# Sheet3.net
KiCad netlist of a schematic drawn in Altium Designer
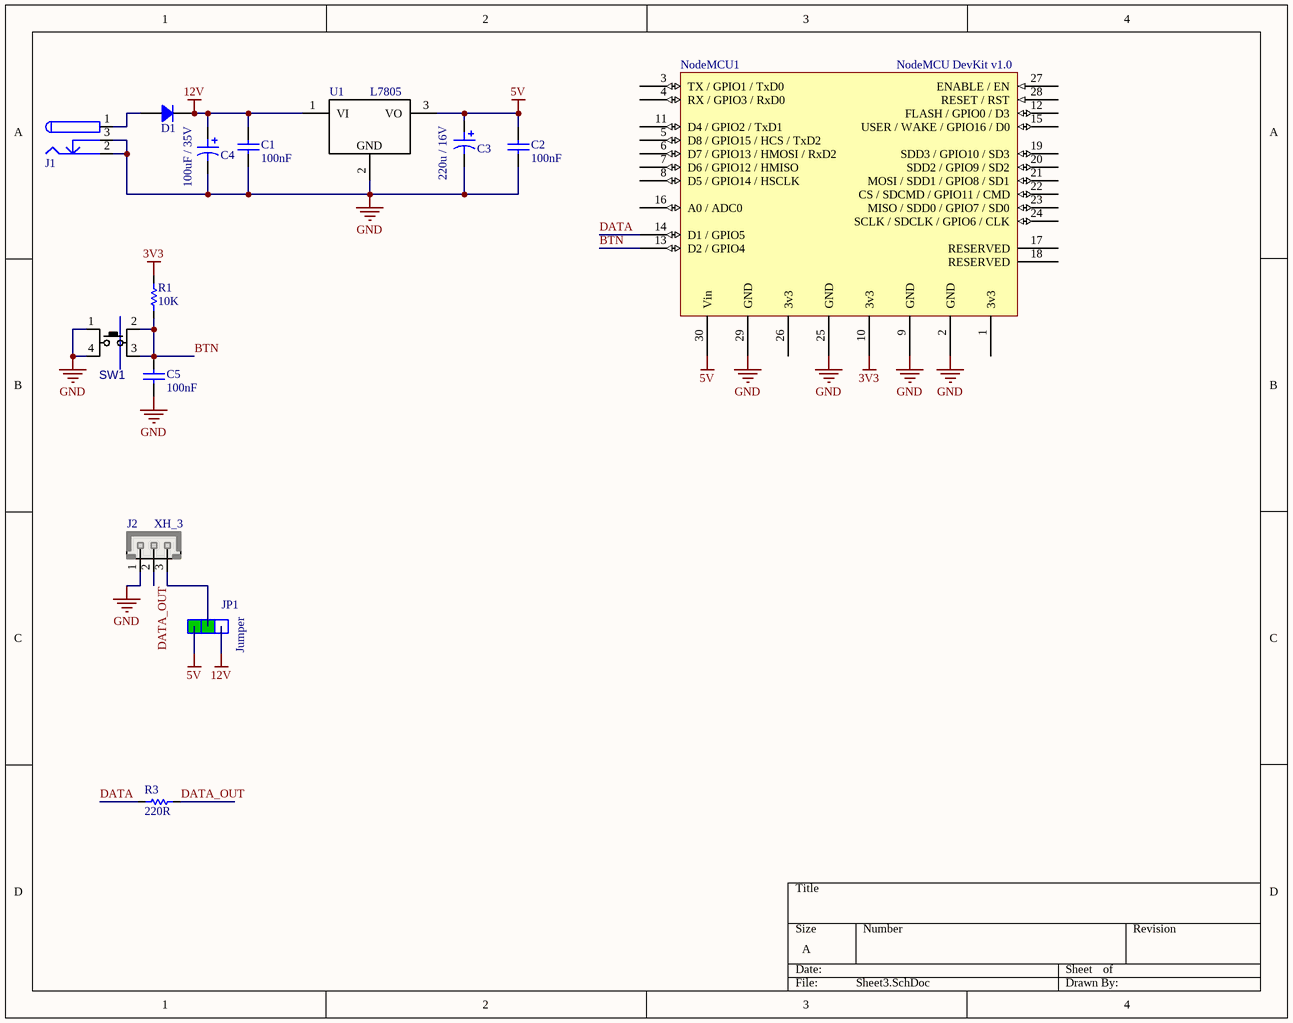
[diagram p0: Sheet3.SchDoc]

(export (version "E")
  (design (tool "Eeschema 10.0.6"))
  (components
    (comp (ref "C1")
      (value "100nF")
      (footprint "CAPC4817X12N")
      (description "CAP 1206")
      (fields (field (name "DESIGNER") "Abbas Basereh"))
      (libsource (lib "4_5924601381297062174") (part "CAP SMD 1206"))
    )
    (comp (ref "C2")
      (value "100nF")
      (footprint "CAPC4817X12N")
      (description "CAP 1206")
      (fields (field (name "DESIGNER") "Abbas Basereh"))
      (libsource (lib "4_5924601381297062174") (part "CAP SMD 1206"))
    )
    (comp (ref "C3")
      (value "220u / 16V")
      (footprint "Cap electrolitic radial 8x12-3.5")
      (description "Cap electrolitic radial")
      (fields (field (name "DESIGNER") "Abbas Basereh"))
      (libsource (lib "4_5924601381297062174") (part "Cap ELECTROLITIC TOTAL SIZE"))
    )
    (comp (ref "C4")
      (value "100uF / 35V")
      (footprint "Cap electrolitic radial 10x20-5")
      (description "Cap electrolitic radial")
      (fields (field (name "DESIGNER") "Abbas Basereh"))
      (libsource (lib "4_5924601381297062174") (part "Cap ELECTROLITIC TOTAL SIZE"))
    )
    (comp (ref "C5")
      (value "100nF")
      (footprint "CAPC4817X12N")
      (description "CAP 1206")
      (fields (field (name "DESIGNER") "Abbas Basereh"))
      (libsource (lib "4_5924601381297062174") (part "CAP SMD 1206"))
    )
    (comp (ref "D1")
      (value "1N4007")
      (footprint "DO41 P7.5MM")
      (description "Diode Standard 1000V 1A Through Hole DO-204AL (DO-41)")
      (libsource (lib "Diode") (part "1N4007 (THD)"))
    )
    (comp (ref "J1")
      (value "DC Power Jack")
      (footprint "DC Power Jack 1")
      (description "DC Power Jack. Center Pin 2.5mm. Diameter: 5.7mm")
      (fields (field (name "DESIGNER") "Ali Hafizi"))
      (libsource (lib "4_5965406465417019807") (part "DC Power Jack"))
    )
    (comp (ref "J2")
      (value "XH_3")
      (footprint "XH_3")
      (description "PW10-x-M, JST-BxB-XH-A pitch: 2.5mm, 3A/250v")
      (fields (field (name "MANF") "JST") (field (name "MANF_P#") "B3B-XH-A"))
      (libsource (lib "Library_Package") (part "XH_3"))
    )
    (comp (ref "JP1")
      (value "Jumper")
      (footprint "jumper selector")
      (description "Jumper Selector")
      (libsource (lib "4_5965406465417019807") (part "Jumper Selector"))
    )
    (comp (ref "NodeMCU1")
      (value "NodeMCU DevKit v1.0")
      (footprint "NODEMCU")
      (libsource (lib "Personal-Altium-Library-master") (part "NodeMCU DevKit v1.0"))
    )
    (comp (ref "R1")
      (value "10K")
      (footprint "Res-(1/4)")
      (description "Resistor")
      (fields (field (name "TOLERANCE") "5%") (field (name "POWER") "1/4 W"))
      (libsource (lib "AltiumLib1 (1)") (part "Resistor"))
    )
    (comp (ref "R3")
      (value "220R")
      (footprint "Res-(1/4)")
      (description "Resistor")
      (fields (field (name "TOLERANCE") "5%") (field (name "POWER") "1/4 W"))
      (libsource (lib "AltiumLib1 (1)") (part "Resistor"))
    )
    (comp (ref "SW1")
      (value "PUSHBUTTON")
      (footprint "SWPBT_SPDT_10X10X7")
      (description "SWITCH, PUSH BUTTON, TACTILE, THD, SPDT, 10X10X7mm")
      (libsource (lib "Library_Package") (part "SWPBT_SPDT_10X10X7"))
    )
    (comp (ref "U1")
      (value "L7805")
      (footprint "to220-123-v")
      (description "LINEAR REGULATOR 5.0V")
      (libsource (lib "General_05") (part "L7805-TO220"))
    )
  )
  (nets
    (net (code "1") (name "/BTN") (class "Default")
      (node (ref "C5") (pin "1") (pinfunction "1_1") (pintype "passive"))
      (node (ref "NodeMCU1") (pin "13") (pinfunction "D2_/_GPIO4_13") (pintype "bidirectional"))
      (node (ref "R1") (pin "1") (pinfunction "1_1") (pintype "passive"))
      (node (ref "SW1") (pin "2") (pinfunction "P3_2") (pintype "passive"))
      (node (ref "SW1") (pin "3") (pinfunction "P4_3") (pintype "passive"))
    )
    (net (code "2") (name "/DATA") (class "Default")
      (node (ref "NodeMCU1") (pin "14") (pinfunction "D1_/_GPIO5_14") (pintype "bidirectional"))
      (node (ref "R3") (pin "1") (pinfunction "1_1") (pintype "passive"))
    )
    (net (code "3") (name "/DATA_OUT") (class "Default")
      (node (ref "J2") (pin "2") (pinfunction "2_2") (pintype "passive"))
      (node (ref "R3") (pin "2") (pinfunction "2_2") (pintype "passive"))
    )
    (net (code "4") (name "3V3") (class "Default")
      (node (ref "NodeMCU1") (pin "10") (pinfunction "3v3_10") (pintype "power_in"))
      (node (ref "R1") (pin "2") (pinfunction "2_2") (pintype "passive"))
    )
    (net (code "5") (name "5V") (class "Default")
      (node (ref "C2") (pin "1") (pinfunction "1_1") (pintype "passive"))
      (node (ref "C3") (pin "1") (pinfunction "1_1") (pintype "passive"))
      (node (ref "JP1") (pin "1") (pinfunction "1_1") (pintype "passive"))
      (node (ref "NodeMCU1") (pin "30") (pinfunction "Vin_30") (pintype "passive"))
      (node (ref "U1") (pin "3") (pinfunction "VO_3") (pintype "passive"))
    )
    (net (code "6") (name "12V") (class "Default")
      (node (ref "C1") (pin "2") (pinfunction "2_2") (pintype "passive"))
      (node (ref "C4") (pin "1") (pinfunction "1_1") (pintype "passive"))
      (node (ref "D1") (pin "2") (pinfunction "2_2") (pintype "passive"))
      (node (ref "JP1") (pin "3") (pinfunction "3_3") (pintype "passive"))
      (node (ref "U1") (pin "1") (pinfunction "VI_1") (pintype "passive"))
    )
    (net (code "7") (name "GND") (class "Default")
      (node (ref "C1") (pin "1") (pinfunction "1_1") (pintype "passive"))
      (node (ref "C2") (pin "2") (pinfunction "2_2") (pintype "passive"))
      (node (ref "C3") (pin "2") (pinfunction "2_2") (pintype "passive"))
      (node (ref "C4") (pin "2") (pinfunction "2_2") (pintype "passive"))
      (node (ref "C5") (pin "2") (pinfunction "2_2") (pintype "passive"))
      (node (ref "J1") (pin "2") (pinfunction "2_2") (pintype "power_in"))
      (node (ref "J1") (pin "3") (pinfunction "3_3") (pintype "power_in"))
      (node (ref "J2") (pin "1") (pinfunction "1_1") (pintype "passive"))
      (node (ref "NodeMCU1") (pin "2") (pinfunction "GND_2") (pintype "power_in"))
      (node (ref "NodeMCU1") (pin "25") (pinfunction "GND_25") (pintype "power_in"))
      (node (ref "NodeMCU1") (pin "29") (pinfunction "GND_29") (pintype "passive"))
      (node (ref "NodeMCU1") (pin "9") (pinfunction "GND_9") (pintype "power_in"))
      (node (ref "SW1") (pin "1") (pinfunction "P1_1") (pintype "passive"))
      (node (ref "SW1") (pin "4") (pinfunction "P2_4") (pintype "passive"))
      (node (ref "U1") (pin "2") (pintype "passive"))
    )
    (net (code "8") (name "Net-(D1-Pad1)") (class "Default")
      (node (ref "D1") (pin "1") (pinfunction "1_1") (pintype "passive"))
      (node (ref "J1") (pin "1") (pinfunction "1_1") (pintype "power_in"))
    )
    (net (code "9") (name "Net-(J2-Pad3)") (class "Default")
      (node (ref "J2") (pin "3") (pinfunction "3_3") (pintype "passive"))
      (node (ref "JP1") (pin "2") (pinfunction "2_2") (pintype "passive"))
    )
    (net (code "10") (name "unconnected-(NodeMCU1-3v3-Pad1)") (class "Default")
      (node (ref "NodeMCU1") (pin "1") (pinfunction "3v3_1") (pintype "power_in"))
    )
    (net (code "11") (name "unconnected-(NodeMCU1-3v3-Pad26)") (class "Default")
      (node (ref "NodeMCU1") (pin "26") (pinfunction "3v3_26") (pintype "power_in"))
    )
    (net (code "12") (name "unconnected-(NodeMCU1-A0_{slash}_ADC0-Pad16)") (class "Default")
      (node (ref "NodeMCU1") (pin "16") (pinfunction "A0_/_ADC0_16") (pintype "bidirectional"))
    )
    (net (code "13") (name "unconnected-(NodeMCU1-CS_{slash}_SDCMD_{slash}_GPIO11_{slash}_CMD-Pad22)") (class "Default")
      (node (ref "NodeMCU1") (pin "22") (pinfunction "CS_/_SDCMD_/_GPIO11_/_CMD_22") (pintype "bidirectional"))
    )
    (net (code "14") (name "unconnected-(NodeMCU1-D4_{slash}_GPIO2_{slash}_TxD1-Pad11)") (class "Default")
      (node (ref "NodeMCU1") (pin "11") (pinfunction "D4_/_GPIO2_/_TxD1_11") (pintype "bidirectional"))
    )
    (net (code "15") (name "unconnected-(NodeMCU1-D5_{slash}_GPIO14_{slash}_HSCLK-Pad8)") (class "Default")
      (node (ref "NodeMCU1") (pin "8") (pinfunction "D5_/_GPIO14_/_HSCLK_8") (pintype "bidirectional"))
    )
    (net (code "16") (name "unconnected-(NodeMCU1-D6_{slash}_GPIO12_{slash}_HMISO-Pad7)") (class "Default")
      (node (ref "NodeMCU1") (pin "7") (pinfunction "D6_/_GPIO12_/_HMISO_7") (pintype "bidirectional"))
    )
    (net (code "17") (name "unconnected-(NodeMCU1-D7_{slash}_GPIO13_{slash}_HMOSI_{slash}_RxD2-Pad6)") (class "Default")
      (node (ref "NodeMCU1") (pin "6") (pinfunction "D7_/_GPIO13_/_HMOSI_/_RxD2_6") (pintype "bidirectional"))
    )
    (net (code "18") (name "unconnected-(NodeMCU1-D8_{slash}_GPIO15_{slash}_HCS_{slash}_TxD2-Pad5)") (class "Default")
      (node (ref "NodeMCU1") (pin "5") (pinfunction "D8_/_GPIO15_/_HCS_/_TxD2_5") (pintype "bidirectional"))
    )
    (net (code "19") (name "unconnected-(NodeMCU1-ENABLE_{slash}_EN-Pad27)") (class "Default")
      (node (ref "NodeMCU1") (pin "27") (pinfunction "ENABLE_/_EN_27") (pintype "input"))
    )
    (net (code "20") (name "unconnected-(NodeMCU1-FLASH_{slash}_GPIO0_{slash}_D3-Pad12)") (class "Default")
      (node (ref "NodeMCU1") (pin "12") (pinfunction "FLASH_/_GPIO0_/_D3_12") (pintype "bidirectional"))
    )
    (net (code "21") (name "unconnected-(NodeMCU1-MISO_{slash}_SDD0_{slash}_GPIO7_{slash}_SD0-Pad23)") (class "Default")
      (node (ref "NodeMCU1") (pin "23") (pinfunction "MISO_/_SDD0_/_GPIO7_/_SD0_23") (pintype "bidirectional"))
    )
    (net (code "22") (name "unconnected-(NodeMCU1-MOSI_{slash}_SDD1_{slash}_GPIO8_{slash}_SD1-Pad21)") (class "Default")
      (node (ref "NodeMCU1") (pin "21") (pinfunction "MOSI_/_SDD1_/_GPIO8_/_SD1_21") (pintype "bidirectional"))
    )
    (net (code "23") (name "unconnected-(NodeMCU1-RESERVED-Pad17)") (class "Default")
      (node (ref "NodeMCU1") (pin "17") (pinfunction "RESERVED_17") (pintype "passive"))
    )
    (net (code "24") (name "unconnected-(NodeMCU1-RESERVED-Pad18)") (class "Default")
      (node (ref "NodeMCU1") (pin "18") (pinfunction "RESERVED_18") (pintype "passive"))
    )
    (net (code "25") (name "unconnected-(NodeMCU1-RESET_{slash}_RST-Pad28)") (class "Default")
      (node (ref "NodeMCU1") (pin "28") (pinfunction "RESET_/_RST_28") (pintype "input"))
    )
    (net (code "26") (name "unconnected-(NodeMCU1-RX_{slash}_GPIO3_{slash}_RxD0-Pad4)") (class "Default")
      (node (ref "NodeMCU1") (pin "4") (pinfunction "RX_/_GPIO3_/_RxD0_4") (pintype "bidirectional"))
    )
    (net (code "27") (name "unconnected-(NodeMCU1-SCLK_{slash}_SDCLK_{slash}_GPIO6_{slash}_CLK-Pad24)") (class "Default")
      (node (ref "NodeMCU1") (pin "24") (pinfunction "SCLK_/_SDCLK_/_GPIO6_/_CLK_24") (pintype "bidirectional"))
    )
    (net (code "28") (name "unconnected-(NodeMCU1-SDD2_{slash}_GPIO9_{slash}_SD2-Pad20)") (class "Default")
      (node (ref "NodeMCU1") (pin "20") (pinfunction "SDD2_/_GPIO9_/_SD2_20") (pintype "bidirectional"))
    )
    (net (code "29") (name "unconnected-(NodeMCU1-SDD3_{slash}_GPIO10_{slash}_SD3-Pad19)") (class "Default")
      (node (ref "NodeMCU1") (pin "19") (pinfunction "SDD3_/_GPIO10_/_SD3_19") (pintype "bidirectional"))
    )
    (net (code "30") (name "unconnected-(NodeMCU1-TX_{slash}_GPIO1_{slash}_TxD0-Pad3)") (class "Default")
      (node (ref "NodeMCU1") (pin "3") (pinfunction "TX_/_GPIO1_/_TxD0_3") (pintype "bidirectional"))
    )
    (net (code "31") (name "unconnected-(NodeMCU1-USER_{slash}_WAKE_{slash}_GPIO16_{slash}_D0-Pad15)") (class "Default")
      (node (ref "NodeMCU1") (pin "15") (pinfunction "USER_/_WAKE_/_GPIO16_/_D0_15") (pintype "bidirectional"))
    )
  )
)
